# mcu_module.net
KiCad netlist of a schematic drawn in Altium Designer
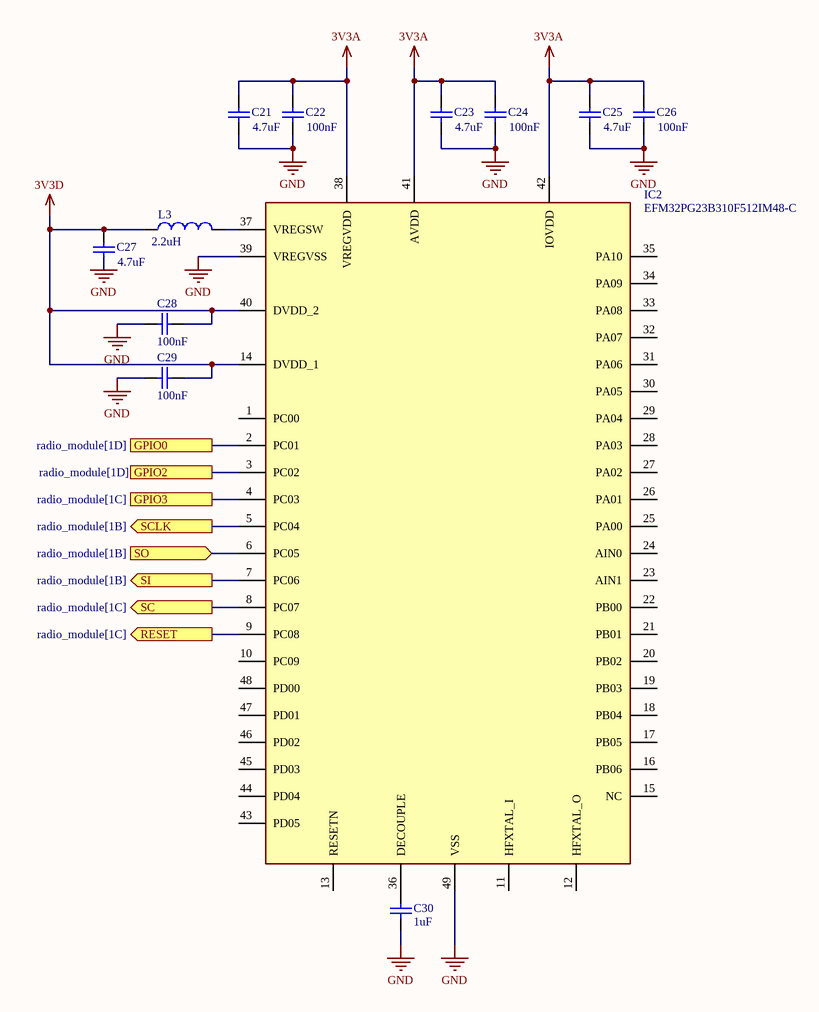
[diagram p0: mcu_module.SchDoc]

(export (version "E")
  (design (tool "Eeschema 10.0.6"))
  (components
    (comp (ref "C21")
      (value "4.7uF")
      (footprint "CAPC1608X92X38LL15T08")
      (fields (field (name "MANUFACTURER") "Vitramon") (field (name "PART NUMBER") "VJ0603D3R9CXPAJ"))
      (libsource (lib "Altium Content Vault") (part "CAP"))
    )
    (comp (ref "C22")
      (value "100nF")
      (footprint "CAPC1608X92X38LL15T08")
      (fields (field (name "MANUFACTURER") "Vitramon") (field (name "PART NUMBER") "VJ0603D3R9CXPAJ"))
      (libsource (lib "Altium Content Vault") (part "CAP"))
    )
    (comp (ref "C23")
      (value "4.7uF")
      (footprint "CAPC1608X92X38LL15T08")
      (fields (field (name "MANUFACTURER") "Vitramon") (field (name "PART NUMBER") "VJ0603D3R9CXPAJ"))
      (libsource (lib "Altium Content Vault") (part "CAP"))
    )
    (comp (ref "C24")
      (value "100nF")
      (footprint "CAPC1608X92X38LL15T08")
      (fields (field (name "MANUFACTURER") "Vitramon") (field (name "PART NUMBER") "VJ0603D3R9CXPAJ"))
      (libsource (lib "Altium Content Vault") (part "CAP"))
    )
    (comp (ref "C25")
      (value "4.7uF")
      (footprint "CAPC1608X92X38LL15T08")
      (fields (field (name "MANUFACTURER") "Vitramon") (field (name "PART NUMBER") "VJ0603D3R9CXPAJ"))
      (libsource (lib "Altium Content Vault") (part "CAP"))
    )
    (comp (ref "C26")
      (value "100nF")
      (footprint "CAPC1608X92X38LL15T08")
      (fields (field (name "MANUFACTURER") "Vitramon") (field (name "PART NUMBER") "VJ0603D3R9CXPAJ"))
      (libsource (lib "Altium Content Vault") (part "CAP"))
    )
    (comp (ref "C27")
      (value "4.7uF")
      (footprint "CAPC1608X92X38LL15T08")
      (fields (field (name "MANUFACTURER") "Vitramon") (field (name "PART NUMBER") "VJ0603D3R9CXPAJ"))
      (libsource (lib "Altium Content Vault") (part "CAP"))
    )
    (comp (ref "C28")
      (value "100nF")
      (footprint "CAPC1608X92X38LL15T08")
      (fields (field (name "MANUFACTURER") "Vitramon") (field (name "PART NUMBER") "VJ0603D3R9CXPAJ"))
      (libsource (lib "Altium Content Vault") (part "CAP"))
    )
    (comp (ref "C29")
      (value "100nF")
      (footprint "CAPC1608X92X38LL15T08")
      (fields (field (name "MANUFACTURER") "Vitramon") (field (name "PART NUMBER") "VJ0603D3R9CXPAJ"))
      (libsource (lib "Altium Content Vault") (part "CAP"))
    )
    (comp (ref "C30")
      (value "1uF")
      (footprint "CAPC1608X92X38LL15T08")
      (fields (field (name "MANUFACTURER") "Vitramon") (field (name "PART NUMBER") "VJ0603D3R9CXPAJ"))
      (libsource (lib "Altium Content Vault") (part "CAP"))
    )
    (comp (ref "IC2")
      (value "EFM32PG23B310F512IM48-C")
      (footprint "SamacSys:QFN40P600X600X90-49N-D")
      (description "Integrated Circuit")
      (fields (field (name "MOUSER PART NUMBER") "634-PG23310F512IM48C"))
      (libsource (lib "SamacSys") (part "EFM32PG23B310F512IM48-C"))
    )
    (comp (ref "L3")
      (value "7447860115G")
      (footprint "WE-MK_0603_L1.6W0.8H0.8")
      (fields (field (name "INDUCTANCE") "2.2uH"))
      (libsource (lib "Altium Content Vault") (part "Inductor - 1"))
    )
  )
  (nets
    (net (code "1") (name "/GPIO0") (class "Default")
      (node (ref "IC2") (pin "2") (pinfunction "PC01_2") (pintype "passive"))
    )
    (net (code "2") (name "/GPIO2") (class "Default")
      (node (ref "IC2") (pin "3") (pinfunction "PC02_3") (pintype "passive"))
    )
    (net (code "3") (name "/GPIO3") (class "Default")
      (node (ref "IC2") (pin "4") (pinfunction "PC03_4") (pintype "passive"))
    )
    (net (code "4") (name "/RESET") (class "Default")
      (node (ref "IC2") (pin "9") (pinfunction "PC08_9") (pintype "passive"))
    )
    (net (code "5") (name "/SC") (class "Default")
      (node (ref "IC2") (pin "8") (pinfunction "PC07_8") (pintype "passive"))
    )
    (net (code "6") (name "/SCLK") (class "Default")
      (node (ref "IC2") (pin "5") (pinfunction "PC04_5") (pintype "passive"))
    )
    (net (code "7") (name "/SI") (class "Default")
      (node (ref "IC2") (pin "7") (pinfunction "PC06_7") (pintype "passive"))
    )
    (net (code "8") (name "/SO") (class "Default")
      (node (ref "IC2") (pin "6") (pinfunction "PC05_6") (pintype "passive"))
    )
    (net (code "9") (name "3V3A") (class "Default")
      (node (ref "C21") (pin "2") (pinfunction "2_2") (pintype "passive"))
      (node (ref "C22") (pin "2") (pinfunction "2_2") (pintype "passive"))
      (node (ref "C23") (pin "2") (pinfunction "2_2") (pintype "passive"))
      (node (ref "C24") (pin "2") (pinfunction "2_2") (pintype "passive"))
      (node (ref "C25") (pin "2") (pinfunction "2_2") (pintype "passive"))
      (node (ref "C26") (pin "2") (pinfunction "2_2") (pintype "passive"))
      (node (ref "IC2") (pin "38") (pinfunction "VREGVDD_38") (pintype "passive"))
      (node (ref "IC2") (pin "41") (pinfunction "AVDD_41") (pintype "passive"))
      (node (ref "IC2") (pin "42") (pinfunction "IOVDD_42") (pintype "passive"))
    )
    (net (code "10") (name "3V3D") (class "Default")
      (node (ref "C27") (pin "2") (pinfunction "2_2") (pintype "passive"))
      (node (ref "C28") (pin "1") (pinfunction "1_1") (pintype "passive"))
      (node (ref "C29") (pin "1") (pinfunction "1_1") (pintype "passive"))
      (node (ref "IC2") (pin "14") (pinfunction "DVDD_1_14") (pintype "passive"))
      (node (ref "IC2") (pin "40") (pinfunction "DVDD_2_40") (pintype "passive"))
      (node (ref "L3") (pin "1") (pinfunction "1_1") (pintype "passive"))
    )
    (net (code "11") (name "GND") (class "Default")
      (node (ref "C21") (pin "1") (pinfunction "1_1") (pintype "passive"))
      (node (ref "C22") (pin "1") (pinfunction "1_1") (pintype "passive"))
      (node (ref "C23") (pin "1") (pinfunction "1_1") (pintype "passive"))
      (node (ref "C24") (pin "1") (pinfunction "1_1") (pintype "passive"))
      (node (ref "C25") (pin "1") (pinfunction "1_1") (pintype "passive"))
      (node (ref "C26") (pin "1") (pinfunction "1_1") (pintype "passive"))
      (node (ref "C27") (pin "1") (pinfunction "1_1") (pintype "passive"))
      (node (ref "C28") (pin "2") (pinfunction "2_2") (pintype "passive"))
      (node (ref "C29") (pin "2") (pinfunction "2_2") (pintype "passive"))
      (node (ref "C30") (pin "2") (pinfunction "2_2") (pintype "passive"))
      (node (ref "IC2") (pin "39") (pinfunction "VREGVSS_39") (pintype "passive"))
      (node (ref "IC2") (pin "49") (pinfunction "VSS_49") (pintype "passive"))
    )
    (net (code "12") (name "Net-(IC2-DECOUPLE)") (class "Default")
      (node (ref "C30") (pin "1") (pinfunction "1_1") (pintype "passive"))
      (node (ref "IC2") (pin "36") (pinfunction "DECOUPLE_36") (pintype "passive"))
    )
    (net (code "13") (name "Net-(IC2-VREGSW)") (class "Default")
      (node (ref "IC2") (pin "37") (pinfunction "VREGSW_37") (pintype "passive"))
      (node (ref "L3") (pin "2") (pinfunction "2_2") (pintype "passive"))
    )
    (net (code "14") (name "unconnected-(IC2-AIN0-Pad24)") (class "Default")
      (node (ref "IC2") (pin "24") (pinfunction "AIN0_24") (pintype "passive"))
    )
    (net (code "15") (name "unconnected-(IC2-AIN1-Pad23)") (class "Default")
      (node (ref "IC2") (pin "23") (pinfunction "AIN1_23") (pintype "passive"))
    )
    (net (code "16") (name "unconnected-(IC2-HFXTAL_I-Pad11)") (class "Default")
      (node (ref "IC2") (pin "11") (pinfunction "HFXTAL_I_11") (pintype "passive"))
    )
    (net (code "17") (name "unconnected-(IC2-HFXTAL_O-Pad12)") (class "Default")
      (node (ref "IC2") (pin "12") (pinfunction "HFXTAL_O_12") (pintype "passive"))
    )
    (net (code "18") (name "unconnected-(IC2-NC-Pad15)") (class "Default")
      (node (ref "IC2") (pin "15") (pinfunction "NC_15") (pintype "passive"))
    )
    (net (code "19") (name "unconnected-(IC2-PA00-Pad25)") (class "Default")
      (node (ref "IC2") (pin "25") (pinfunction "PA00_25") (pintype "passive"))
    )
    (net (code "20") (name "unconnected-(IC2-PA01-Pad26)") (class "Default")
      (node (ref "IC2") (pin "26") (pinfunction "PA01_26") (pintype "passive"))
    )
    (net (code "21") (name "unconnected-(IC2-PA02-Pad27)") (class "Default")
      (node (ref "IC2") (pin "27") (pinfunction "PA02_27") (pintype "passive"))
    )
    (net (code "22") (name "unconnected-(IC2-PA03-Pad28)") (class "Default")
      (node (ref "IC2") (pin "28") (pinfunction "PA03_28") (pintype "passive"))
    )
    (net (code "23") (name "unconnected-(IC2-PA04-Pad29)") (class "Default")
      (node (ref "IC2") (pin "29") (pinfunction "PA04_29") (pintype "passive"))
    )
    (net (code "24") (name "unconnected-(IC2-PA05-Pad30)") (class "Default")
      (node (ref "IC2") (pin "30") (pinfunction "PA05_30") (pintype "passive"))
    )
    (net (code "25") (name "unconnected-(IC2-PA06-Pad31)") (class "Default")
      (node (ref "IC2") (pin "31") (pinfunction "PA06_31") (pintype "passive"))
    )
    (net (code "26") (name "unconnected-(IC2-PA07-Pad32)") (class "Default")
      (node (ref "IC2") (pin "32") (pinfunction "PA07_32") (pintype "passive"))
    )
    (net (code "27") (name "unconnected-(IC2-PA08-Pad33)") (class "Default")
      (node (ref "IC2") (pin "33") (pinfunction "PA08_33") (pintype "passive"))
    )
    (net (code "28") (name "unconnected-(IC2-PA09-Pad34)") (class "Default")
      (node (ref "IC2") (pin "34") (pinfunction "PA09_34") (pintype "passive"))
    )
    (net (code "29") (name "unconnected-(IC2-PA10-Pad35)") (class "Default")
      (node (ref "IC2") (pin "35") (pinfunction "PA10_35") (pintype "passive"))
    )
    (net (code "30") (name "unconnected-(IC2-PB00-Pad22)") (class "Default")
      (node (ref "IC2") (pin "22") (pinfunction "PB00_22") (pintype "passive"))
    )
    (net (code "31") (name "unconnected-(IC2-PB01-Pad21)") (class "Default")
      (node (ref "IC2") (pin "21") (pinfunction "PB01_21") (pintype "passive"))
    )
    (net (code "32") (name "unconnected-(IC2-PB02-Pad20)") (class "Default")
      (node (ref "IC2") (pin "20") (pinfunction "PB02_20") (pintype "passive"))
    )
    (net (code "33") (name "unconnected-(IC2-PB03-Pad19)") (class "Default")
      (node (ref "IC2") (pin "19") (pinfunction "PB03_19") (pintype "passive"))
    )
    (net (code "34") (name "unconnected-(IC2-PB04-Pad18)") (class "Default")
      (node (ref "IC2") (pin "18") (pinfunction "PB04_18") (pintype "passive"))
    )
    (net (code "35") (name "unconnected-(IC2-PB05-Pad17)") (class "Default")
      (node (ref "IC2") (pin "17") (pinfunction "PB05_17") (pintype "passive"))
    )
    (net (code "36") (name "unconnected-(IC2-PB06-Pad16)") (class "Default")
      (node (ref "IC2") (pin "16") (pinfunction "PB06_16") (pintype "passive"))
    )
    (net (code "37") (name "unconnected-(IC2-PC00-Pad1)") (class "Default")
      (node (ref "IC2") (pin "1") (pinfunction "PC00_1") (pintype "passive"))
    )
    (net (code "38") (name "unconnected-(IC2-PC09-Pad10)") (class "Default")
      (node (ref "IC2") (pin "10") (pinfunction "PC09_10") (pintype "passive"))
    )
    (net (code "39") (name "unconnected-(IC2-PD00-Pad48)") (class "Default")
      (node (ref "IC2") (pin "48") (pinfunction "PD00_48") (pintype "passive"))
    )
    (net (code "40") (name "unconnected-(IC2-PD01-Pad47)") (class "Default")
      (node (ref "IC2") (pin "47") (pinfunction "PD01_47") (pintype "passive"))
    )
    (net (code "41") (name "unconnected-(IC2-PD02-Pad46)") (class "Default")
      (node (ref "IC2") (pin "46") (pinfunction "PD02_46") (pintype "passive"))
    )
    (net (code "42") (name "unconnected-(IC2-PD03-Pad45)") (class "Default")
      (node (ref "IC2") (pin "45") (pinfunction "PD03_45") (pintype "passive"))
    )
    (net (code "43") (name "unconnected-(IC2-PD04-Pad44)") (class "Default")
      (node (ref "IC2") (pin "44") (pinfunction "PD04_44") (pintype "passive"))
    )
    (net (code "44") (name "unconnected-(IC2-PD05-Pad43)") (class "Default")
      (node (ref "IC2") (pin "43") (pinfunction "PD05_43") (pintype "passive"))
    )
    (net (code "45") (name "unconnected-(IC2-RESETN-Pad13)") (class "Default")
      (node (ref "IC2") (pin "13") (pinfunction "RESETN_13") (pintype "passive"))
    )
  )
)
